# CH1-Input.net
KiCad netlist of a schematic drawn in Altium Designer
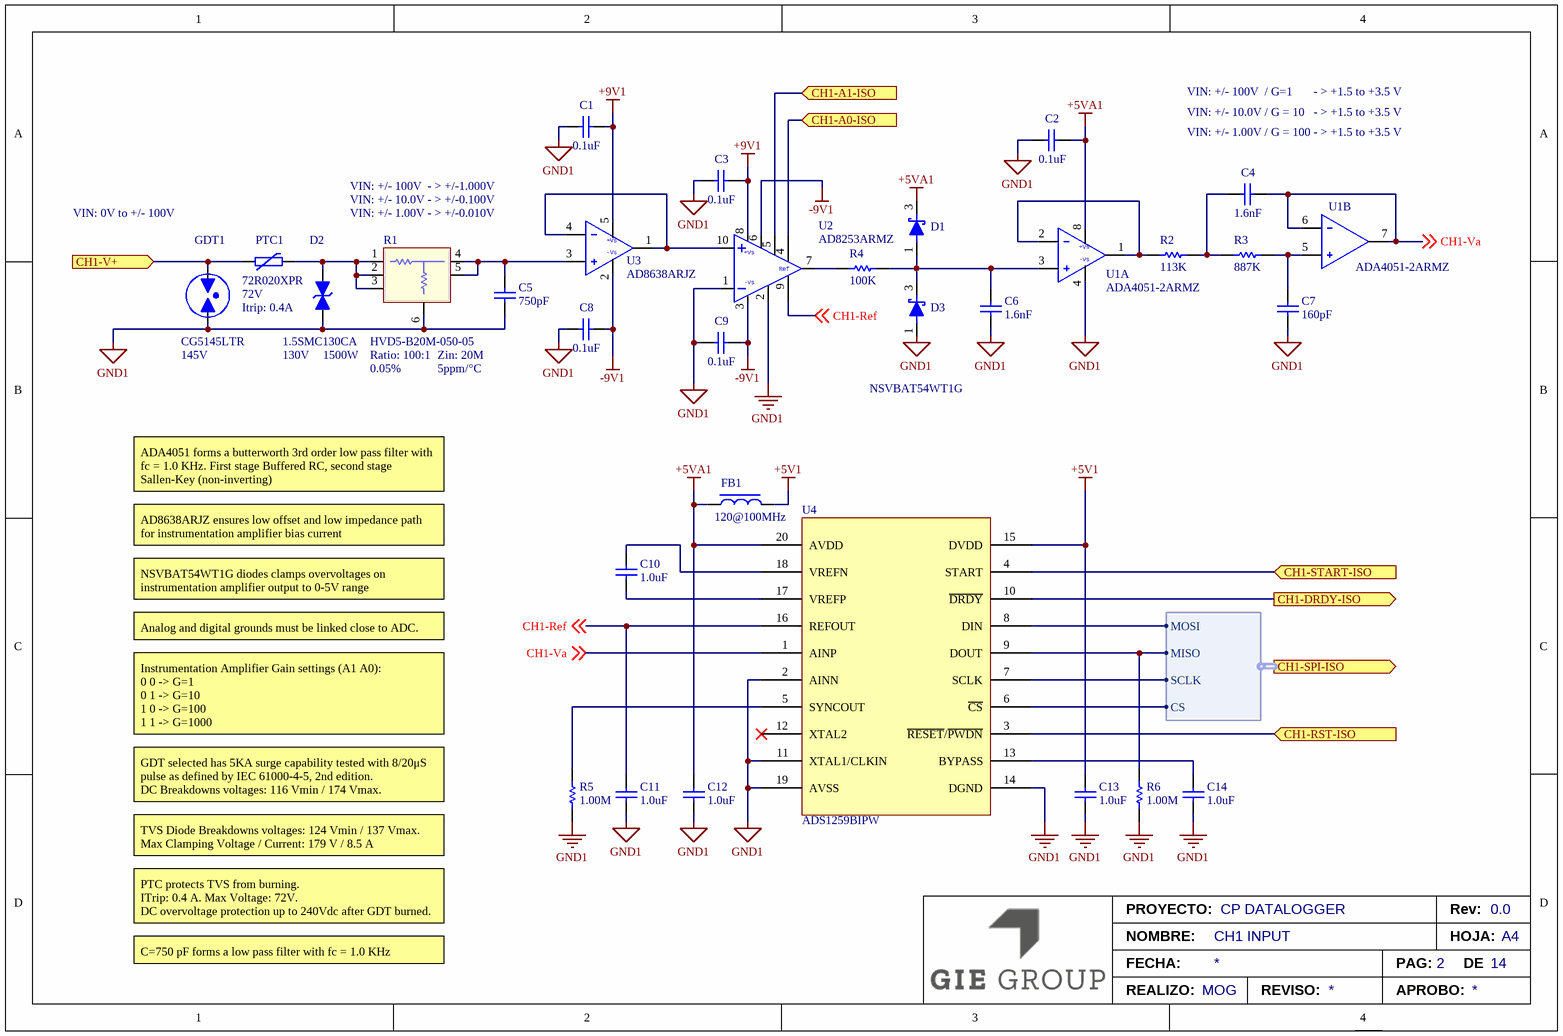
[diagram p0: CH1-Input.SchDoc]

(export (version "E")
  (design (tool "Eeschema 10.0.6"))
  (components
    (comp (ref "C1")
      (value "0.1uF")
      (footprint "CAP-0603")
      (description "CAP CER 0.1uF 50V X7R 0603")
      (fields (field (name "PARTNUMBER") "C0603C104K5RACAUTO") (field (name "MANUFACTURER") "Kemet"))
      (libsource (lib "Kemet") (part "C0603C104K5RACAUTO"))
    )
    (comp (ref "C2")
      (value "0.1uF")
      (footprint "CAP-0603")
      (description "CAP CER 0.1uF 50V X7R 0603")
      (fields (field (name "PARTNUMBER") "C0603C104K5RACAUTO") (field (name "MANUFACTURER") "Kemet"))
      (libsource (lib "Kemet") (part "C0603C104K5RACAUTO"))
    )
    (comp (ref "C3")
      (value "0.1uF")
      (footprint "CAP-0603")
      (description "CAP CER 0.1uF 50V X7R 0603")
      (fields (field (name "PARTNUMBER") "C0603C104K5RACAUTO") (field (name "MANUFACTURER") "Kemet"))
      (libsource (lib "Kemet") (part "C0603C104K5RACAUTO"))
    )
    (comp (ref "C4")
      (value "1.6nF")
      (footprint "CAP-0603")
      (description "CAP CER 1600´pF 50V C0G 0603")
      (fields (field (name "PARTNUMBER") "C0603C162J5GAC7867") (field (name "MANUFACTURER") "Kemet"))
      (libsource (lib "Kemet") (part "C0603C162J5GAC7867"))
    )
    (comp (ref "C5")
      (value "750pF")
      (footprint "CAP-0603")
      (description "CAP CER 750´pF 50V C0G 0603")
      (fields (field (name "PARTNUMBER") "C0603C161J1GAC7867") (field (name "MANUFACTURER") "Kemet"))
      (libsource (lib "Kemet") (part "C0603C751J5GAC7867"))
    )
    (comp (ref "C6")
      (value "1.6nF")
      (footprint "CAP-0603")
      (description "CAP CER 1600´pF 50V C0G 0603")
      (fields (field (name "PARTNUMBER") "C0603C162J5GAC7867") (field (name "MANUFACTURER") "Kemet"))
      (libsource (lib "Kemet") (part "C0603C162J5GAC7867"))
    )
    (comp (ref "C7")
      (value "160pF")
      (footprint "CAP-0603")
      (description "CAP CER 160 pF 100V C0G 0603")
      (fields (field (name "PARTNUMBER") "C0603C161J1GAC7867") (field (name "MANUFACTURER") "Kemet"))
      (libsource (lib "Kemet") (part "C0603C161J1GAC7867"))
    )
    (comp (ref "C8")
      (value "0.1uF")
      (footprint "CAP-0603")
      (description "CAP CER 0.1uF 50V X7R 0603")
      (fields (field (name "PARTNUMBER") "C0603C104K5RACAUTO") (field (name "MANUFACTURER") "Kemet"))
      (libsource (lib "Kemet") (part "C0603C104K5RACAUTO"))
    )
    (comp (ref "C9")
      (value "0.1uF")
      (footprint "CAP-0603")
      (description "CAP CER 0.1uF 50V X7R 0603")
      (fields (field (name "PARTNUMBER") "C0603C104K5RACAUTO") (field (name "MANUFACTURER") "Kemet"))
      (libsource (lib "Kemet") (part "C0603C104K5RACAUTO"))
    )
    (comp (ref "C10")
      (value "1.0uF")
      (footprint "CAP-0603")
      (description "CAP CER 1uF 25V X7R 0603")
      (fields (field (name "PARTNUMBER") "C0603C105M3RAC7867") (field (name "MANUFACTURER") "Kemet"))
      (libsource (lib "Kemet") (part "C0603C105M3RAC7867"))
    )
    (comp (ref "C11")
      (value "1.0uF")
      (footprint "CAP-0603")
      (description "CAP CER 1uF 25V X7R 0603")
      (fields (field (name "PARTNUMBER") "C0603C105M3RAC7867") (field (name "MANUFACTURER") "Kemet"))
      (libsource (lib "Kemet") (part "C0603C105M3RAC7867"))
    )
    (comp (ref "C12")
      (value "1.0uF")
      (footprint "CAP-0603")
      (description "CAP CER 1uF 25V X7R 0603")
      (fields (field (name "PARTNUMBER") "C0603C105M3RAC7867") (field (name "MANUFACTURER") "Kemet"))
      (libsource (lib "Kemet") (part "C0603C105M3RAC7867"))
    )
    (comp (ref "C13")
      (value "1.0uF")
      (footprint "CAP-0603")
      (description "CAP CER 1uF 25V X7R 0603")
      (fields (field (name "PARTNUMBER") "C0603C105M3RAC7867") (field (name "MANUFACTURER") "Kemet"))
      (libsource (lib "Kemet") (part "C0603C105M3RAC7867"))
    )
    (comp (ref "C14")
      (value "1.0uF")
      (footprint "CAP-0603")
      (description "CAP CER 1uF 25V X7R 0603")
      (fields (field (name "PARTNUMBER") "C0603C105M3RAC7867") (field (name "MANUFACTURER") "Kemet"))
      (libsource (lib "Kemet") (part "C0603C105M3RAC7867"))
    )
    (comp (ref "D1")
      (value "NSVBAT54WT1G")
      (footprint "SOT-323-3")
      (description "Schottky Diode 30V 200mA SOT323")
      (fields (field (name "MANUFACTURER") "OnSemiconductor"))
      (libsource (lib "OnSemiconductors") (part "NSVBAT54WT1G"))
    )
    (comp (ref "D2")
      (value "1.5SMC130CA")
      (footprint "SMC - BIIDIR")
      (description "TVS Diode 1.5kW 130V 5% Bi-Directional")
      (fields
        (field (name "MANUFACTURER") "Littelfuse")
        (field (name "PARTNUMBER") "1.5SMC130CA")
        (field (name "VOLTAGE") "130V")
        (field (name "POWER") "1500W")
      )
      (libsource (lib "Littlelfuse") (part "1.5SMC130CA"))
    )
    (comp (ref "D3")
      (value "NSVBAT54WT1G")
      (footprint "SOT-323-3")
      (description "Schottky Diode 30V 200mA SOT323")
      (fields (field (name "MANUFACTURER") "OnSemiconductor") (field (name "PARTNUMBER") "NSVBAT54WT1G"))
      (libsource (lib "OnSemiconductors") (part "NSVBAT54WT1G"))
    )
    (comp (ref "FB1")
      (value "120@100MHz")
      (footprint "IND-0603")
      (description "Ferrite Bead 120Ohms 900mA 25% DCR=130m")
      (fields (field (name "MANUFACTURER") "Kemet") (field (name "PARTNUMBER") "Z0603C121GPWZT"))
      (libsource (lib "Kemet") (part "Z0603C121GPWZT"))
    )
    (comp (ref "GDT1")
      (value "CG5145LTR")
      (footprint "LITTLELFUSE-CG5XXXLTR")
      (description "Gas Discharge Tube 145V")
      (fields
        (field (name "MANUFACTURER") "Littelfuse")
        (field (name "PARTNUMBER") "CG5145LTR")
        (field (name "VOLTAGE") "145V")
      )
      (libsource (lib "Littlelfuse") (part "CG5145LTR"))
    )
    (comp (ref "PTC1")
      (value "72R020XPR")
      (footprint "LITTLELFUSE-72R020X")
      (description "PTC Polyfuse Radial 72V 0.2A")
      (fields
        (field (name "MANUFACTURER") "Littlelfuse")
        (field (name "PARTNUMBER") "72R020XPR")
        (field (name "VOLTAGE") "72V")
        (field (name "ITRIP") "0.4A")
      )
      (libsource (lib "Littlelfuse") (part "72R020XPR"))
    )
    (comp (ref "R1")
      (value "HVD5-B20M-050-05")
      (footprint "CADDOCK - HVD5-B20M-050-05")
      (description "20M ohm 0.05% 5ppm Voltage Divider")
      (fields
        (field (name "MANUFACTURER") "Caddock")
        (field (name "PARTNUMBER") "HVD5-B20M-050-05")
        (field (name "THERMAL") "5ppm/°C")
        (field (name "TOLERANCE") "0.05%")
        (field (name "RATIO") "100:1")
        (field (name "ZIN") "20M")
      )
      (libsource (lib "Caddock") (part "HVD5-B20M-050-05"))
    )
    (comp (ref "R2")
      (value "113K")
      (footprint "RES-0603")
      (description "RES SMD 113K OHM 1% 1/10W 0603")
      (fields (field (name "TOLERANCE") "1%") (field (name "MANUFACTURER") "Yageo"))
      (libsource (lib "Yageo") (part "RC0603FR-07113KL"))
    )
    (comp (ref "R3")
      (value "887K")
      (footprint "RES-0603")
      (description "RES SMD 887K OHM 1% 1/10W 0603")
      (fields (field (name "TOLERANCE") "1%") (field (name "MANUFACTURER") "Yageo"))
      (libsource (lib "Yageo") (part "RC0603FR-07887KL"))
    )
    (comp (ref "R4")
      (value "100K")
      (footprint "RES-0603")
      (description "RES SMD 100K OHM 1% 1/10W 0603")
      (fields (field (name "TOLERANCE") "1%") (field (name "MANUFACTURER") "Yageo"))
      (libsource (lib "Yageo") (part "RC0603FR-07100KL"))
    )
    (comp (ref "R5")
      (value "1.00M")
      (footprint "RES-0603")
      (description "RES SMD 1M OHM 1% 1/10W 0603")
      (fields (field (name "TOLERANCE") "1%") (field (name "MANUFACTURER") "Yageo"))
      (libsource (lib "Yageo") (part "RC0603FR-071ML"))
    )
    (comp (ref "R6")
      (value "1.00M")
      (footprint "RES-0603")
      (description "RES SMD 1M OHM 1% 1/10W 0603")
      (fields (field (name "TOLERANCE") "1%") (field (name "MANUFACTURER") "Yageo"))
      (libsource (lib "Yageo") (part "RC0603FR-071ML"))
    )
    (comp (ref "U1")
      (value "ADA4051-2ARMZ")
      (footprint "MSOP8")
      (description "Dual  Precision Amplifier Micro Power Auto Zero")
      (fields (field (name "MANUFACTURER") "Analog Devices") (field (name "PARTNUMBER") "ADA4051-2ARMZ"))
      (libsource (lib "AnalogDevices") (part "ADA4051-2ARMZ"))
    )
    (comp (ref "U2")
      (value "AD8253ARMZ")
      (footprint "MSOP10")
      (description "Instrumentation Amplifiers High Speed Programmable High Gain In-Amp")
      (fields (field (name "MANUFACTURER") "Analog Devices Inc"))
      (libsource (lib "AnalogDevices") (part "AD8253ARMZ"))
    )
    (comp (ref "U3")
      (value "AD8638ARJZ")
      (footprint "SOT23-5")
      (description "16V Auto-Zero CMOS Amplifier")
      (fields (field (name "MANUFACTURER") "Analog Devices") (field (name "PARTNUMBER") "AD8638ARJZ"))
      (libsource (lib "AnalogDevices") (part "AD8638ARJZ"))
    )
    (comp (ref "U4")
      (value "ADS1259BIPW")
      (footprint "TSSOP20")
      (description "Analog to Digital Converter 14.4kSPS 24-Bit")
      (fields (field (name "MANUFACTURER") "Texas Instruments") (field (name "PARTNUMBER") "ADS1259BIPW"))
      (libsource (lib "TexasInstruments") (part "ADS1259BIPW"))
    )
  )
  (nets
    (net (code "2") (name "+5V1") (class "Default")
      (node (ref "C13") (pin "2") (pinfunction "2_2") (pintype "passive"))
      (node (ref "FB1") (pin "2") (pinfunction "2_2") (pintype "passive"))
      (node (ref "U4") (pin "15") (pinfunction "DVDD_15") (pintype "power_in"))
    )
    (net (code "3") (name "+5VA1") (class "Default")
      (node (ref "C12") (pin "2") (pinfunction "2_2") (pintype "passive"))
      (node (ref "C2") (pin "2") (pinfunction "2_2") (pintype "passive"))
      (node (ref "D1") (pin "3") (pinfunction "K_3") (pintype "passive"))
      (node (ref "FB1") (pin "1") (pinfunction "1_1") (pintype "passive"))
      (node (ref "U1") (pin "8") (pinfunction "+VS_8") (pintype "power_in"))
      (node (ref "U4") (pin "20") (pinfunction "AVDD_20") (pintype "power_in"))
    )
    (net (code "4") (name "+9V1") (class "Default")
      (node (ref "C1") (pin "2") (pinfunction "2_2") (pintype "passive"))
      (node (ref "C3") (pin "2") (pinfunction "2_2") (pintype "passive"))
      (node (ref "U2") (pin "8") (pinfunction "+Vs_8") (pintype "passive"))
      (node (ref "U3") (pin "5") (pinfunction "+VS_5") (pintype "power_in"))
    )
    (net (code "5") (name "-9V1") (class "Default")
      (node (ref "C8") (pin "2") (pinfunction "2_2") (pintype "passive"))
      (node (ref "C9") (pin "2") (pinfunction "2_2") (pintype "passive"))
      (node (ref "U2") (pin "3") (pinfunction "-Vs_3") (pintype "passive"))
      (node (ref "U2") (pin "6") (pinfunction "WR_6") (pintype "passive"))
      (node (ref "U3") (pin "2") (pinfunction "-Vs_2") (pintype "power_in"))
    )
    (net (code "6") (name "/CH1-A0-ISO") (class "Default")
      (node (ref "U2") (pin "4") (pinfunction "A0_4") (pintype "passive"))
    )
    (net (code "7") (name "/CH1-A1-ISO") (class "Default")
      (node (ref "U2") (pin "5") (pinfunction "A1_5") (pintype "passive"))
    )
    (net (code "8") (name "/CH1-DRDY-ISO") (class "Default")
      (node (ref "U4") (pin "10") (pinfunction "~{DRDY}_10") (pintype "power_in"))
    )
    (net (code "9") (name "/CH1-RST-ISO") (class "Default")
      (node (ref "U4") (pin "3") (pinfunction "~{RESET}/~{PWDN}_3") (pintype "power_in"))
    )
    (net (code "10") (name "/CH1-START-ISO") (class "Default")
      (node (ref "U4") (pin "4") (pinfunction "START_4") (pintype "power_in"))
    )
    (net (code "11") (name "/CH1-V+") (class "Default")
      (node (ref "GDT1") (pin "1") (pinfunction "A_1") (pintype "passive"))
      (node (ref "PTC1") (pin "1") (pinfunction "1_1") (pintype "passive"))
    )
    (net (code "12") (name "/CS") (class "Default")
      (node (ref "U4") (pin "6") (pinfunction "~{CS}_6") (pintype "power_in"))
    )
    (net (code "13") (name "/MISO") (class "Default")
      (node (ref "R6") (pin "2") (pinfunction "2_2") (pintype "passive"))
      (node (ref "U4") (pin "9") (pinfunction "DOUT_9") (pintype "power_in"))
    )
    (net (code "14") (name "/MOSI") (class "Default")
      (node (ref "U4") (pin "8") (pinfunction "DIN_8") (pintype "power_in"))
    )
    (net (code "15") (name "/SCLK") (class "Default")
      (node (ref "U4") (pin "7") (pinfunction "SCLK_7") (pintype "power_in"))
    )
    (net (code "17") (name "CH1-Ref") (class "Default")
      (node (ref "C11") (pin "2") (pinfunction "2_2") (pintype "passive"))
      (node (ref "U2") (pin "9") (pinfunction "REF_9") (pintype "passive"))
      (node (ref "U4") (pin "16") (pinfunction "REFOUT_16") (pintype "power_in"))
    )
    (net (code "18") (name "CH1-Va") (class "Default")
      (node (ref "C4") (pin "1") (pinfunction "1_1") (pintype "passive"))
      (node (ref "U1") (pin "6") (pinfunction "-INB_6") (pintype "passive"))
      (node (ref "U1") (pin "7") (pinfunction "OUTB_7") (pintype "passive"))
      (node (ref "U4") (pin "1") (pinfunction "AINP_1") (pintype "passive"))
    )
    (net (code "19") (name "GND1") (class "Default")
      (node (ref "C1") (pin "1") (pinfunction "1_1") (pintype "passive"))
      (node (ref "C11") (pin "1") (pinfunction "1_1") (pintype "passive"))
      (node (ref "C12") (pin "1") (pinfunction "1_1") (pintype "passive"))
      (node (ref "C13") (pin "1") (pinfunction "1_1") (pintype "passive"))
      (node (ref "C14") (pin "1") (pinfunction "1_1") (pintype "passive"))
      (node (ref "C2") (pin "1") (pinfunction "1_1") (pintype "passive"))
      (node (ref "C3") (pin "1") (pinfunction "1_1") (pintype "passive"))
      (node (ref "C5") (pin "1") (pinfunction "1_1") (pintype "passive"))
      (node (ref "C6") (pin "1") (pinfunction "1_1") (pintype "passive"))
      (node (ref "C7") (pin "1") (pinfunction "1_1") (pintype "passive"))
      (node (ref "C8") (pin "1") (pinfunction "1_1") (pintype "passive"))
      (node (ref "C9") (pin "1") (pinfunction "1_1") (pintype "passive"))
      (node (ref "D2") (pin "2") (pinfunction "K_2") (pintype "passive"))
      (node (ref "D3") (pin "1") (pinfunction "A_1") (pintype "passive"))
      (node (ref "GDT1") (pin "2") (pinfunction "K_2") (pintype "passive"))
      (node (ref "R1") (pin "6") (pinfunction "6_6") (pintype "passive"))
      (node (ref "R5") (pin "1") (pinfunction "1_1") (pintype "passive"))
      (node (ref "R6") (pin "1") (pinfunction "1_1") (pintype "passive"))
      (node (ref "U1") (pin "4") (pinfunction "-Vs_4") (pintype "power_in"))
      (node (ref "U2") (pin "1") (pinfunction "-_IN_1") (pintype "passive"))
      (node (ref "U2") (pin "2") (pinfunction "DGND_2") (pintype "passive"))
      (node (ref "U4") (pin "11") (pinfunction "XTAL1/CLKIN_11") (pintype "power_in"))
      (node (ref "U4") (pin "14") (pinfunction "DGND_14") (pintype "power_in"))
      (node (ref "U4") (pin "19") (pinfunction "AVSS_19") (pintype "power_in"))
      (node (ref "U4") (pin "2") (pinfunction "AINN_2") (pintype "passive"))
    )
    (net (code "20") (name "Net-(C4-Pad2)") (class "Default")
      (node (ref "C4") (pin "2") (pinfunction "2_2") (pintype "passive"))
      (node (ref "R2") (pin "2") (pinfunction "2_2") (pintype "passive"))
      (node (ref "R3") (pin "1") (pinfunction "1_1") (pintype "passive"))
    )
    (net (code "21") (name "Net-(D1-A)") (class "Default")
      (node (ref "C6") (pin "2") (pinfunction "2_2") (pintype "passive"))
      (node (ref "D1") (pin "1") (pinfunction "A_1") (pintype "passive"))
      (node (ref "D3") (pin "3") (pinfunction "K_3") (pintype "passive"))
      (node (ref "R4") (pin "2") (pinfunction "2_2") (pintype "passive"))
      (node (ref "U1") (pin "3") (pinfunction "+INA_3") (pintype "passive"))
    )
    (net (code "22") (name "Net-(D2-A)") (class "Default")
      (node (ref "D2") (pin "1") (pinfunction "A_1") (pintype "passive"))
      (node (ref "PTC1") (pin "2") (pinfunction "2_2") (pintype "passive"))
      (node (ref "R1") (pin "1") (pinfunction "1_1") (pintype "passive"))
      (node (ref "R1") (pin "2") (pinfunction "2_2") (pintype "passive"))
      (node (ref "R1") (pin "3") (pinfunction "3_3") (pintype "passive"))
    )
    (net (code "23") (name "Net-(U1A--INA)") (class "Default")
      (node (ref "R2") (pin "1") (pinfunction "1_1") (pintype "passive"))
      (node (ref "U1") (pin "1") (pinfunction "OUTA_1") (pintype "passive"))
      (node (ref "U1") (pin "2") (pinfunction "-INA_2") (pintype "passive"))
    )
    (net (code "24") (name "Net-(U1B-+INB)") (class "Default")
      (node (ref "C7") (pin "2") (pinfunction "2_2") (pintype "passive"))
      (node (ref "R3") (pin "2") (pinfunction "2_2") (pintype "passive"))
      (node (ref "U1") (pin "5") (pinfunction "+INB_5") (pintype "passive"))
    )
    (net (code "25") (name "Net-(U2-+_IN)") (class "Default")
      (node (ref "U2") (pin "10") (pinfunction "+_IN_10") (pintype "passive"))
      (node (ref "U3") (pin "1") (pinfunction "OUT_1") (pintype "passive"))
      (node (ref "U3") (pin "4") (pinfunction "-IN_4") (pintype "passive"))
    )
    (net (code "26") (name "Net-(U2-OUT)") (class "Default")
      (node (ref "R4") (pin "1") (pinfunction "1_1") (pintype "passive"))
      (node (ref "U2") (pin "7") (pinfunction "OUT_7") (pintype "passive"))
    )
    (net (code "27") (name "Net-(U3-+IN)") (class "Default")
      (node (ref "C5") (pin "2") (pinfunction "2_2") (pintype "passive"))
      (node (ref "R1") (pin "4") (pinfunction "4_4") (pintype "passive"))
      (node (ref "R1") (pin "5") (pinfunction "5_5") (pintype "passive"))
      (node (ref "U3") (pin "3") (pinfunction "+IN_3") (pintype "passive"))
    )
    (net (code "28") (name "Net-(U4-BYPASS)") (class "Default")
      (node (ref "C14") (pin "2") (pinfunction "2_2") (pintype "passive"))
      (node (ref "U4") (pin "13") (pinfunction "BYPASS_13") (pintype "power_in"))
    )
    (net (code "29") (name "Net-(U4-SYNCOUT)") (class "Default")
      (node (ref "R5") (pin "2") (pinfunction "2_2") (pintype "passive"))
      (node (ref "U4") (pin "5") (pinfunction "SYNCOUT_5") (pintype "passive"))
    )
    (net (code "30") (name "Net-(U4-VREFN)") (class "Default")
      (node (ref "C10") (pin "2") (pinfunction "2_2") (pintype "passive"))
      (node (ref "U4") (pin "18") (pinfunction "VREFN_18") (pintype "power_in"))
    )
    (net (code "31") (name "Net-(U4-VREFP)") (class "Default")
      (node (ref "C10") (pin "1") (pinfunction "1_1") (pintype "passive"))
      (node (ref "U4") (pin "17") (pinfunction "VREFP_17") (pintype "power_in"))
    )
    (net (code "32") (name "unconnected-(U4-XTAL2-Pad12)") (class "Default")
      (node (ref "U4") (pin "12") (pinfunction "XTAL2_12") (pintype "power_in+no_connect"))
    )
  )
)
